# interface_board_2.net
KiCad netlist of a schematic drawn in EAGLE
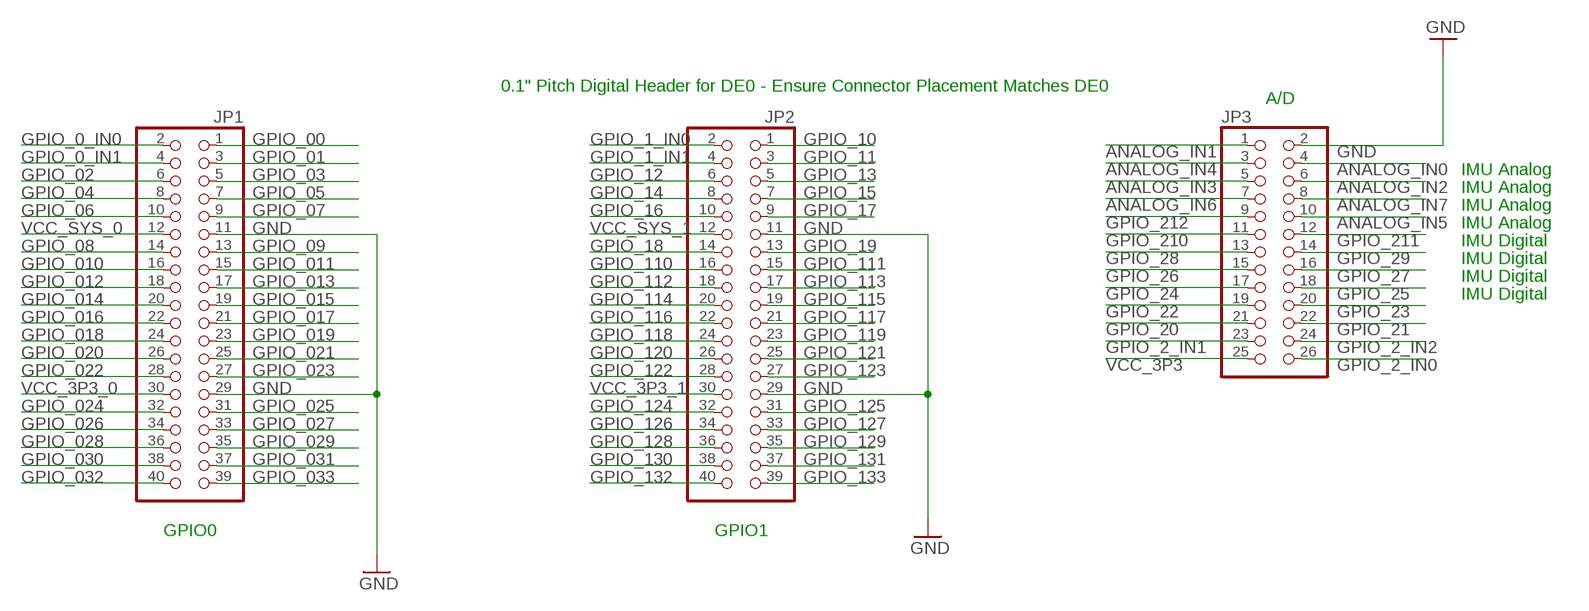
[diagram p0: schematic, sheet 1]
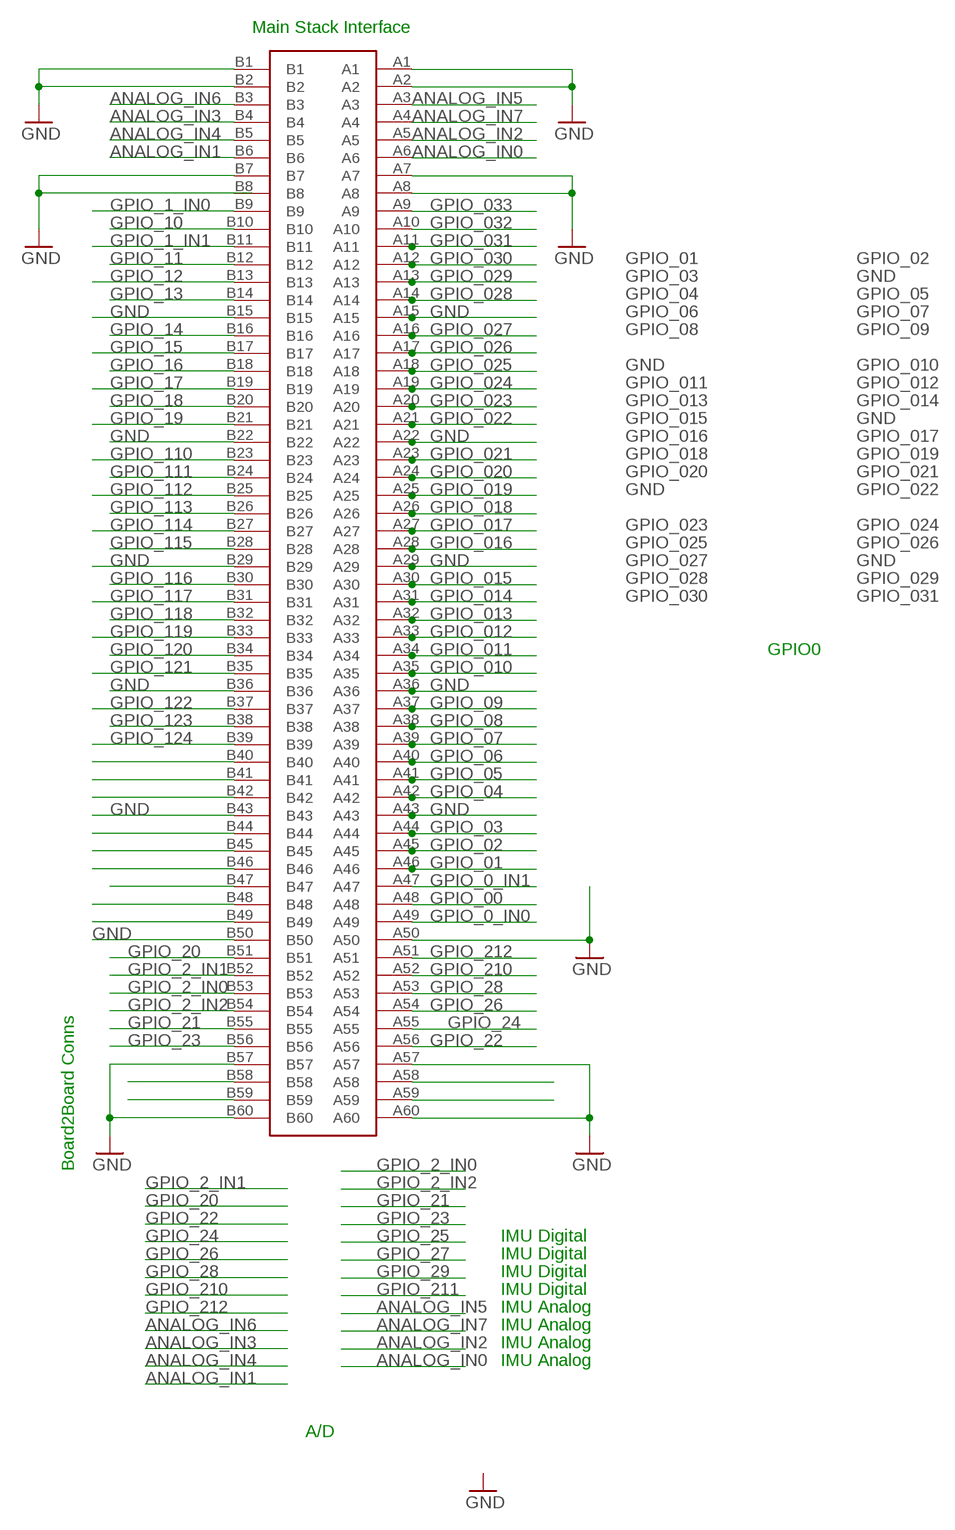
[diagram p1: schematic, sheet 2]
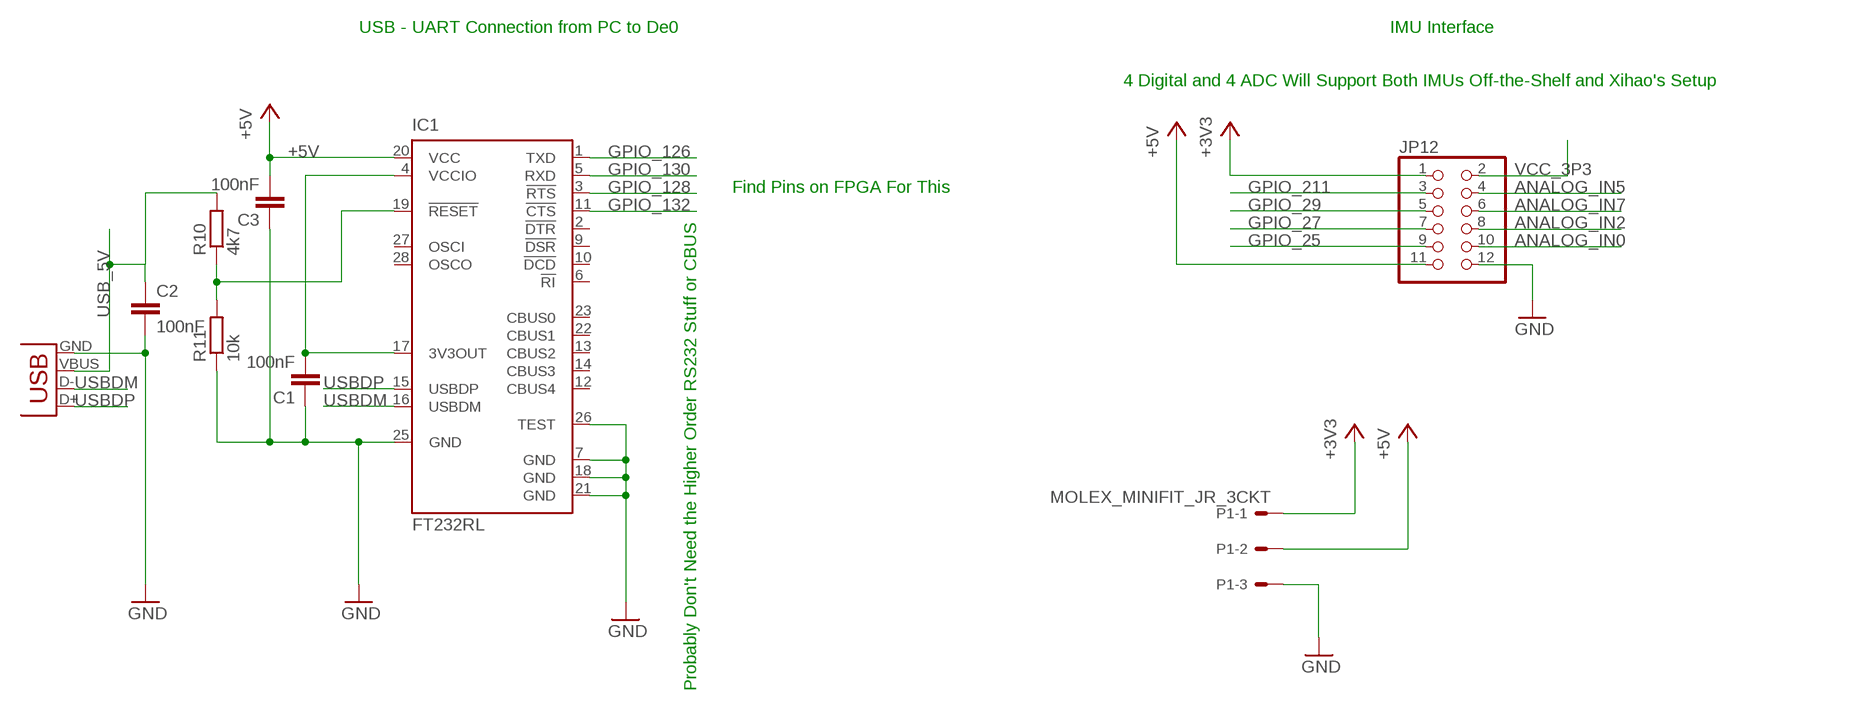
[diagram p2: schematic, sheet 3]
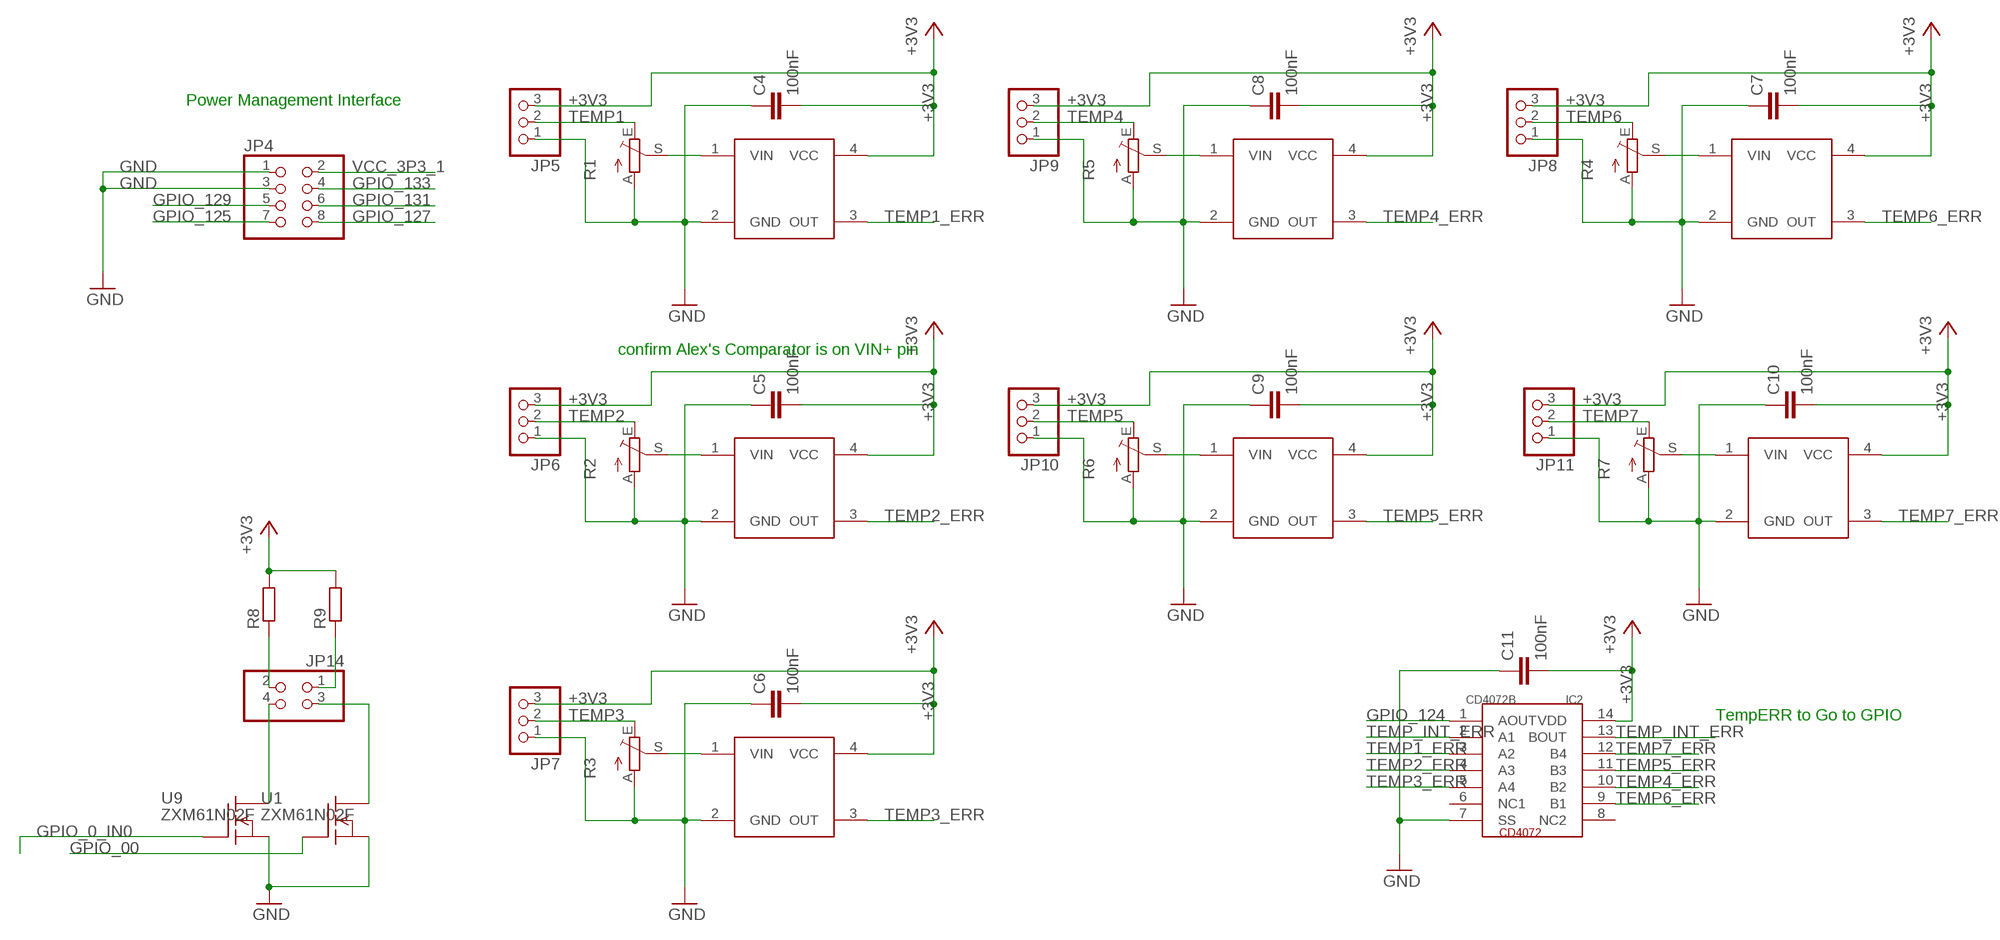
[diagram p3: schematic, sheet 4]

(export (version "E")
  (design (tool "Eeschema 10.0.6"))
  (components
    (comp (ref "C4")
      (value "100nF")
      (footprint "eagle-import:C0805")
      (libsource (lib "eagle-import") (part "C-EUC0805"))
    )
    (comp (ref "C5")
      (value "100nF")
      (footprint "eagle-import:C0805")
      (libsource (lib "eagle-import") (part "C-EUC0805"))
    )
    (comp (ref "C6")
      (value "100nF")
      (footprint "eagle-import:C0805")
      (libsource (lib "eagle-import") (part "C-EUC0805"))
    )
    (comp (ref "C7")
      (value "100nF")
      (footprint "eagle-import:C0805")
      (libsource (lib "eagle-import") (part "C-EUC0805"))
    )
    (comp (ref "C8")
      (value "100nF")
      (footprint "eagle-import:C0805")
      (libsource (lib "eagle-import") (part "C-EUC0805"))
    )
    (comp (ref "C9")
      (value "100nF")
      (footprint "eagle-import:C0805")
      (libsource (lib "eagle-import") (part "C-EUC0805"))
    )
    (comp (ref "C10")
      (value "100nF")
      (footprint "eagle-import:C0805")
      (libsource (lib "eagle-import") (part "C-EUC0805"))
    )
    (comp (ref "C11")
      (value "100nF")
      (footprint "eagle-import:C0805")
      (libsource (lib "eagle-import") (part "C-EUC0805"))
    )
    (comp (ref "IC2")
      (value "CD4072B")
      (footprint "eagle-import:SO14")
      (libsource (lib "eagle-import") (part "CD4072B"))
    )
    (comp (ref "JP4")
      (value "PINHD-2X4")
      (footprint "eagle-import:2X04")
      (libsource (lib "eagle-import") (part "PINHD-2X4"))
    )
    (comp (ref "JP5")
      (value "PINHD-1X3")
      (footprint "eagle-import:1X03")
      (libsource (lib "eagle-import") (part "PINHD-1X3"))
    )
    (comp (ref "JP6")
      (value "PINHD-1X3")
      (footprint "eagle-import:1X03")
      (libsource (lib "eagle-import") (part "PINHD-1X3"))
    )
    (comp (ref "JP7")
      (value "PINHD-1X3")
      (footprint "eagle-import:1X03")
      (libsource (lib "eagle-import") (part "PINHD-1X3"))
    )
    (comp (ref "JP8")
      (value "PINHD-1X3")
      (footprint "eagle-import:1X03")
      (libsource (lib "eagle-import") (part "PINHD-1X3"))
    )
    (comp (ref "JP9")
      (value "PINHD-1X3")
      (footprint "eagle-import:1X03")
      (libsource (lib "eagle-import") (part "PINHD-1X3"))
    )
    (comp (ref "JP10")
      (value "PINHD-1X3")
      (footprint "eagle-import:1X03")
      (libsource (lib "eagle-import") (part "PINHD-1X3"))
    )
    (comp (ref "JP11")
      (value "PINHD-1X3")
      (footprint "eagle-import:1X03")
      (libsource (lib "eagle-import") (part "PINHD-1X3"))
    )
    (comp (ref "JP14")
      (value "PINHD-2X2")
      (footprint "eagle-import:2X02")
      (libsource (lib "eagle-import") (part "PINHD-2X2"))
    )
    (comp (ref "R1")
      (value "TRIM_1234-S64YW")
      (footprint "eagle-import:POT")
      (libsource (lib "eagle-import") (part "TRIM_1234-S64YW"))
    )
    (comp (ref "R2")
      (value "TRIM_1234-S64YW")
      (footprint "eagle-import:POT")
      (libsource (lib "eagle-import") (part "TRIM_1234-S64YW"))
    )
    (comp (ref "R3")
      (value "TRIM_1234-S64YW")
      (footprint "eagle-import:POT")
      (libsource (lib "eagle-import") (part "TRIM_1234-S64YW"))
    )
    (comp (ref "R4")
      (value "TRIM_1234-S64YW")
      (footprint "eagle-import:POT")
      (libsource (lib "eagle-import") (part "TRIM_1234-S64YW"))
    )
    (comp (ref "R5")
      (value "TRIM_1234-S64YW")
      (footprint "eagle-import:POT")
      (libsource (lib "eagle-import") (part "TRIM_1234-S64YW"))
    )
    (comp (ref "R6")
      (value "TRIM_1234-S64YW")
      (footprint "eagle-import:POT")
      (libsource (lib "eagle-import") (part "TRIM_1234-S64YW"))
    )
    (comp (ref "R7")
      (value "TRIM_1234-S64YW")
      (footprint "eagle-import:POT")
      (libsource (lib "eagle-import") (part "TRIM_1234-S64YW"))
    )
    (comp (ref "R8")
      (value "R-EU_M1206")
      (footprint "eagle-import:M1206")
      (libsource (lib "eagle-import") (part "R-EU_M1206"))
    )
    (comp (ref "R9")
      (value "R-EU_M1206")
      (footprint "eagle-import:M1206")
      (libsource (lib "eagle-import") (part "R-EU_M1206"))
    )
    (comp (ref "U$2")
      (value "ADCMP")
      (footprint "eagle-import:ADCMP")
      (libsource (lib "eagle-import") (part "ADCMP"))
    )
    (comp (ref "U$4")
      (value "ADCMP")
      (footprint "eagle-import:ADCMP")
      (libsource (lib "eagle-import") (part "ADCMP"))
    )
    (comp (ref "U$5")
      (value "ADCMP")
      (footprint "eagle-import:ADCMP")
      (libsource (lib "eagle-import") (part "ADCMP"))
    )
    (comp (ref "U$6")
      (value "ADCMP")
      (footprint "eagle-import:ADCMP")
      (libsource (lib "eagle-import") (part "ADCMP"))
    )
    (comp (ref "U$7")
      (value "ADCMP")
      (footprint "eagle-import:ADCMP")
      (libsource (lib "eagle-import") (part "ADCMP"))
    )
    (comp (ref "U$8")
      (value "ADCMP")
      (footprint "eagle-import:ADCMP")
      (libsource (lib "eagle-import") (part "ADCMP"))
    )
    (comp (ref "U$9")
      (value "ADCMP")
      (footprint "eagle-import:ADCMP")
      (libsource (lib "eagle-import") (part "ADCMP"))
    )
    (comp (ref "U1")
      (value "ZXM61N02F")
      (footprint "eagle-import:SOT23W")
      (libsource (lib "eagle-import") (part "ZXM61N02F"))
    )
    (comp (ref "U9")
      (value "ZXM61N02F")
      (footprint "eagle-import:SOT23W")
      (libsource (lib "eagle-import") (part "ZXM61N02F"))
    )
    (comp (ref "JP1")
      (value "PINHD-2X20")
      (footprint "eagle-import:2X20")
      (libsource (lib "eagle-import") (part "PINHD-2X20"))
    )
    (comp (ref "JP2")
      (value "PINHD-2X20")
      (footprint "eagle-import:2X20")
      (libsource (lib "eagle-import") (part "PINHD-2X20"))
    )
    (comp (ref "JP3")
      (value "PINHD-2X13")
      (footprint "eagle-import:2X13")
      (libsource (lib "eagle-import") (part "PINHD-2X13"))
    )
    (comp (ref "U$10")
      (value "MAIN-STACK-CONN-WIDEPITCH")
      (footprint "eagle-import:STACK-CONN-WIDEPITCH")
      (libsource (lib "eagle-import") (part "MAIN-STACK-CONN-WIDEPITCH"))
    )
    (comp (ref "C1")
      (value "100nF")
      (footprint "eagle-import:C0805")
      (libsource (lib "eagle-import") (part "C-EUC0805"))
    )
    (comp (ref "C2")
      (value "100nF")
      (footprint "eagle-import:C0805")
      (libsource (lib "eagle-import") (part "C-EUC0805"))
    )
    (comp (ref "C3")
      (value "100nF")
      (footprint "eagle-import:C0805")
      (libsource (lib "eagle-import") (part "C-EUC0805"))
    )
    (comp (ref "IC1")
      (value "FT232RL")
      (footprint "eagle-import:SSOP28")
      (libsource (lib "eagle-import") (part "FT232RL"))
    )
    (comp (ref "JP12")
      (value "PINHD-2X6")
      (footprint "eagle-import:2X06")
      (libsource (lib "eagle-import") (part "PINHD-2X6"))
    )
    (comp (ref "P1")
      (value "MOLEX_MINIFIT_JR_3CKT")
      (footprint "eagle-import:3CKT_MINIFIT_JR")
      (libsource (lib "eagle-import") (part "MOLEX_MINIFIT_JR_3CKT"))
    )
    (comp (ref "R10")
      (value "4k7")
      (footprint "eagle-import:M0805")
      (libsource (lib "eagle-import") (part "R-EU_M0805"))
    )
    (comp (ref "R11")
      (value "10k")
      (footprint "eagle-import:M0805")
      (libsource (lib "eagle-import") (part "R-EU_M0805"))
    )
    (comp (ref "X1")
      (value "USBSMD")
      (footprint "eagle-import:USB-MINIB")
      (libsource (lib "eagle-import") (part "USBSMD"))
    )
  )
  (nets
    (net (code "1") (name "+3V3") (class "Default")
      (node (ref "C10") (pin "2") (pinfunction "2_2") (pintype "passive"))
      (node (ref "C11") (pin "2") (pinfunction "2_2") (pintype "passive"))
      (node (ref "C4") (pin "2") (pinfunction "2_2") (pintype "passive"))
      (node (ref "C5") (pin "2") (pinfunction "2_2") (pintype "passive"))
      (node (ref "C6") (pin "2") (pinfunction "2_2") (pintype "passive"))
      (node (ref "C7") (pin "2") (pinfunction "2_2") (pintype "passive"))
      (node (ref "C8") (pin "2") (pinfunction "2_2") (pintype "passive"))
      (node (ref "C9") (pin "2") (pinfunction "2_2") (pintype "passive"))
      (node (ref "IC2") (pin "14") (pinfunction "VDD_14") (pintype "bidirectional"))
      (node (ref "JP10") (pin "3") (pinfunction "3_3") (pintype "passive"))
      (node (ref "JP11") (pin "3") (pinfunction "3_3") (pintype "passive"))
      (node (ref "JP12") (pin "1") (pinfunction "1_1") (pintype "passive"))
      (node (ref "JP5") (pin "3") (pinfunction "3_3") (pintype "passive"))
      (node (ref "JP6") (pin "3") (pinfunction "3_3") (pintype "passive"))
      (node (ref "JP7") (pin "3") (pinfunction "3_3") (pintype "passive"))
      (node (ref "JP8") (pin "3") (pinfunction "3_3") (pintype "passive"))
      (node (ref "JP9") (pin "3") (pinfunction "3_3") (pintype "passive"))
      (node (ref "P1") (pin "1") (pinfunction "S_1") (pintype "passive"))
      (node (ref "R8") (pin "2") (pinfunction "2_2") (pintype "passive"))
      (node (ref "R9") (pin "2") (pinfunction "2_2") (pintype "passive"))
      (node (ref "U$2") (pin "4") (pinfunction "VCC_4") (pintype "bidirectional"))
      (node (ref "U$4") (pin "4") (pinfunction "VCC_4") (pintype "bidirectional"))
      (node (ref "U$5") (pin "4") (pinfunction "VCC_4") (pintype "bidirectional"))
      (node (ref "U$6") (pin "4") (pinfunction "VCC_4") (pintype "bidirectional"))
      (node (ref "U$7") (pin "4") (pinfunction "VCC_4") (pintype "bidirectional"))
      (node (ref "U$8") (pin "4") (pinfunction "VCC_4") (pintype "bidirectional"))
      (node (ref "U$9") (pin "4") (pinfunction "VCC_4") (pintype "bidirectional"))
    )
    (net (code "2") (name "+5V") (class "Default")
      (node (ref "C3") (pin "2") (pinfunction "2_2") (pintype "passive"))
      (node (ref "IC1") (pin "20") (pinfunction "VCC_20") (pintype "power_in"))
      (node (ref "JP12") (pin "11") (pinfunction "11_11") (pintype "passive"))
      (node (ref "P1") (pin "2") (pinfunction "S_2") (pintype "passive"))
    )
    (net (code "3") (name "ANALOG_IN0") (class "Default")
      (node (ref "JP12") (pin "10") (pinfunction "10_10") (pintype "passive"))
      (node (ref "JP3") (pin "4") (pinfunction "4_4") (pintype "passive"))
      (node (ref "U$10") (pin "A6") (pinfunction "A6_A6") (pintype "bidirectional"))
    )
    (net (code "4") (name "ANALOG_IN1") (class "Default")
      (node (ref "JP3") (pin "1") (pinfunction "1_1") (pintype "passive"))
      (node (ref "U$10") (pin "B6") (pinfunction "B6_B6") (pintype "bidirectional"))
    )
    (net (code "5") (name "ANALOG_IN2") (class "Default")
      (node (ref "JP12") (pin "8") (pinfunction "8_8") (pintype "passive"))
      (node (ref "JP3") (pin "6") (pinfunction "6_6") (pintype "passive"))
      (node (ref "U$10") (pin "A5") (pinfunction "A5_A5") (pintype "bidirectional"))
    )
    (net (code "6") (name "ANALOG_IN3") (class "Default")
      (node (ref "JP3") (pin "5") (pinfunction "5_5") (pintype "passive"))
      (node (ref "U$10") (pin "B4") (pinfunction "B4_B4") (pintype "bidirectional"))
    )
    (net (code "7") (name "ANALOG_IN4") (class "Default")
      (node (ref "JP3") (pin "3") (pinfunction "3_3") (pintype "passive"))
      (node (ref "U$10") (pin "B5") (pinfunction "B5_B5") (pintype "bidirectional"))
    )
    (net (code "8") (name "ANALOG_IN5") (class "Default")
      (node (ref "JP12") (pin "4") (pinfunction "4_4") (pintype "passive"))
      (node (ref "JP3") (pin "10") (pinfunction "10_10") (pintype "passive"))
      (node (ref "U$10") (pin "A3") (pinfunction "A3_A3") (pintype "bidirectional"))
    )
    (net (code "9") (name "ANALOG_IN6") (class "Default")
      (node (ref "JP3") (pin "7") (pinfunction "7_7") (pintype "passive"))
      (node (ref "U$10") (pin "B3") (pinfunction "B3_B3") (pintype "bidirectional"))
    )
    (net (code "10") (name "ANALOG_IN7") (class "Default")
      (node (ref "JP12") (pin "6") (pinfunction "6_6") (pintype "passive"))
      (node (ref "JP3") (pin "8") (pinfunction "8_8") (pintype "passive"))
      (node (ref "U$10") (pin "A4") (pinfunction "A4_A4") (pintype "bidirectional"))
    )
    (net (code "11") (name "GND") (class "Default")
      (node (ref "C1") (pin "1") (pinfunction "1_1") (pintype "passive"))
      (node (ref "C10") (pin "1") (pinfunction "1_1") (pintype "passive"))
      (node (ref "C11") (pin "1") (pinfunction "1_1") (pintype "passive"))
      (node (ref "C2") (pin "2") (pinfunction "2_2") (pintype "passive"))
      (node (ref "C3") (pin "1") (pinfunction "1_1") (pintype "passive"))
      (node (ref "C4") (pin "1") (pinfunction "1_1") (pintype "passive"))
      (node (ref "C5") (pin "1") (pinfunction "1_1") (pintype "passive"))
      (node (ref "C6") (pin "1") (pinfunction "1_1") (pintype "passive"))
      (node (ref "C7") (pin "1") (pinfunction "1_1") (pintype "passive"))
      (node (ref "C8") (pin "1") (pinfunction "1_1") (pintype "passive"))
      (node (ref "C9") (pin "1") (pinfunction "1_1") (pintype "passive"))
      (node (ref "IC1") (pin "18") (pinfunction "GND_18") (pintype "power_in"))
      (node (ref "IC1") (pin "21") (pinfunction "GND_21") (pintype "power_in"))
      (node (ref "IC1") (pin "25") (pinfunction "GND_25") (pintype "power_in"))
      (node (ref "IC1") (pin "26") (pinfunction "TEST_26") (pintype "input"))
      (node (ref "IC1") (pin "7") (pinfunction "GND_7") (pintype "power_in"))
      (node (ref "IC2") (pin "7") (pinfunction "SS_7") (pintype "bidirectional"))
      (node (ref "JP1") (pin "11") (pinfunction "11_11") (pintype "passive"))
      (node (ref "JP1") (pin "29") (pinfunction "29_29") (pintype "passive"))
      (node (ref "JP10") (pin "1") (pinfunction "1_1") (pintype "passive"))
      (node (ref "JP11") (pin "1") (pinfunction "1_1") (pintype "passive"))
      (node (ref "JP12") (pin "12") (pinfunction "12_12") (pintype "passive"))
      (node (ref "JP2") (pin "11") (pinfunction "11_11") (pintype "passive"))
      (node (ref "JP2") (pin "29") (pinfunction "29_29") (pintype "passive"))
      (node (ref "JP3") (pin "2") (pinfunction "2_2") (pintype "passive"))
      (node (ref "JP4") (pin "1") (pinfunction "1_1") (pintype "passive"))
      (node (ref "JP4") (pin "3") (pinfunction "3_3") (pintype "passive"))
      (node (ref "JP5") (pin "1") (pinfunction "1_1") (pintype "passive"))
      (node (ref "JP6") (pin "1") (pinfunction "1_1") (pintype "passive"))
      (node (ref "JP7") (pin "1") (pinfunction "1_1") (pintype "passive"))
      (node (ref "JP8") (pin "1") (pinfunction "1_1") (pintype "passive"))
      (node (ref "JP9") (pin "1") (pinfunction "1_1") (pintype "passive"))
      (node (ref "P1") (pin "3") (pinfunction "S_3") (pintype "passive"))
      (node (ref "R1") (pin "A") (pinfunction "A_A") (pintype "passive"))
      (node (ref "R11") (pin "1") (pinfunction "1_1") (pintype "passive"))
      (node (ref "R2") (pin "A") (pinfunction "A_A") (pintype "passive"))
      (node (ref "R3") (pin "A") (pinfunction "A_A") (pintype "passive"))
      (node (ref "R4") (pin "A") (pinfunction "A_A") (pintype "passive"))
      (node (ref "R5") (pin "A") (pinfunction "A_A") (pintype "passive"))
      (node (ref "R6") (pin "A") (pinfunction "A_A") (pintype "passive"))
      (node (ref "R7") (pin "A") (pinfunction "A_A") (pintype "passive"))
      (node (ref "U$10") (pin "A1") (pinfunction "A1_A1") (pintype "bidirectional"))
      (node (ref "U$10") (pin "A15") (pinfunction "A15_A15") (pintype "bidirectional"))
      (node (ref "U$10") (pin "A2") (pinfunction "A2_A2") (pintype "bidirectional"))
      (node (ref "U$10") (pin "A22") (pinfunction "A22_A22") (pintype "bidirectional"))
      (node (ref "U$10") (pin "A29") (pinfunction "A29_A29") (pintype "bidirectional"))
      (node (ref "U$10") (pin "A36") (pinfunction "A36_A36") (pintype "bidirectional"))
      (node (ref "U$10") (pin "A43") (pinfunction "A43_A43") (pintype "bidirectional"))
      (node (ref "U$10") (pin "A50") (pinfunction "A50_A50") (pintype "bidirectional"))
      (node (ref "U$10") (pin "A57") (pinfunction "A57_A57") (pintype "bidirectional"))
      (node (ref "U$10") (pin "A60") (pinfunction "A60_A60") (pintype "bidirectional"))
      (node (ref "U$10") (pin "A7") (pinfunction "A7_A7") (pintype "bidirectional"))
      (node (ref "U$10") (pin "A8") (pinfunction "A8_A8") (pintype "bidirectional"))
      (node (ref "U$10") (pin "B1") (pinfunction "B1_B1") (pintype "bidirectional"))
      (node (ref "U$10") (pin "B15") (pinfunction "B15_B15") (pintype "bidirectional"))
      (node (ref "U$10") (pin "B2") (pinfunction "B2_B2") (pintype "bidirectional"))
      (node (ref "U$10") (pin "B22") (pinfunction "B22_B22") (pintype "bidirectional"))
      (node (ref "U$10") (pin "B29") (pinfunction "B29_B29") (pintype "bidirectional"))
      (node (ref "U$10") (pin "B36") (pinfunction "B36_B36") (pintype "bidirectional"))
      (node (ref "U$10") (pin "B43") (pinfunction "B43_B43") (pintype "bidirectional"))
      (node (ref "U$10") (pin "B50") (pinfunction "B50_B50") (pintype "bidirectional"))
      (node (ref "U$10") (pin "B57") (pinfunction "B57_B57") (pintype "bidirectional"))
      (node (ref "U$10") (pin "B60") (pinfunction "B60_B60") (pintype "bidirectional"))
      (node (ref "U$10") (pin "B7") (pinfunction "B7_B7") (pintype "bidirectional"))
      (node (ref "U$2") (pin "2") (pinfunction "GND_2") (pintype "bidirectional"))
      (node (ref "U$4") (pin "2") (pinfunction "GND_2") (pintype "bidirectional"))
      (node (ref "U$5") (pin "2") (pinfunction "GND_2") (pintype "bidirectional"))
      (node (ref "U$6") (pin "2") (pinfunction "GND_2") (pintype "bidirectional"))
      (node (ref "U$7") (pin "2") (pinfunction "GND_2") (pintype "bidirectional"))
      (node (ref "U$8") (pin "2") (pinfunction "GND_2") (pintype "bidirectional"))
      (node (ref "U$9") (pin "2") (pinfunction "GND_2") (pintype "bidirectional"))
      (node (ref "U1") (pin "2") (pinfunction "S_2") (pintype "passive"))
      (node (ref "U9") (pin "2") (pinfunction "S_2") (pintype "passive"))
      (node (ref "X1") (pin "GND") (pinfunction "GND_GND") (pintype "bidirectional"))
    )
    (net (code "12") (name "GPIO_00") (class "Default")
      (node (ref "JP1") (pin "1") (pinfunction "1_1") (pintype "passive"))
      (node (ref "U$10") (pin "A48") (pinfunction "A48_A48") (pintype "bidirectional"))
      (node (ref "U1") (pin "1") (pinfunction "G_1") (pintype "passive"))
    )
    (net (code "13") (name "GPIO_0_IN0") (class "Default")
      (node (ref "JP1") (pin "2") (pinfunction "2_2") (pintype "passive"))
      (node (ref "U$10") (pin "A49") (pinfunction "A49_A49") (pintype "bidirectional"))
      (node (ref "U9") (pin "1") (pinfunction "G_1") (pintype "passive"))
    )
    (net (code "14") (name "GPIO_0_IN1") (class "Default")
      (node (ref "JP1") (pin "4") (pinfunction "4_4") (pintype "passive"))
      (node (ref "U$10") (pin "A47") (pinfunction "A47_A47") (pintype "bidirectional"))
    )
    (net (code "15") (name "GPIO_01") (class "Default")
      (node (ref "JP1") (pin "3") (pinfunction "3_3") (pintype "passive"))
      (node (ref "U$10") (pin "A46") (pinfunction "A46_A46") (pintype "bidirectional"))
    )
    (net (code "16") (name "GPIO_1_IN0") (class "Default")
      (node (ref "JP2") (pin "2") (pinfunction "2_2") (pintype "passive"))
      (node (ref "U$10") (pin "B9") (pinfunction "B9_B9") (pintype "bidirectional"))
    )
    (net (code "17") (name "GPIO_1_IN1") (class "Default")
      (node (ref "JP2") (pin "4") (pinfunction "4_4") (pintype "passive"))
      (node (ref "U$10") (pin "B11") (pinfunction "B11_B11") (pintype "bidirectional"))
    )
    (net (code "18") (name "GPIO_02") (class "Default")
      (node (ref "JP1") (pin "6") (pinfunction "6_6") (pintype "passive"))
      (node (ref "U$10") (pin "A45") (pinfunction "A45_A45") (pintype "bidirectional"))
    )
    (net (code "19") (name "GPIO_2_IN0") (class "Default")
      (node (ref "JP3") (pin "26") (pinfunction "26_26") (pintype "passive"))
      (node (ref "U$10") (pin "B53") (pinfunction "B53_B53") (pintype "bidirectional"))
    )
    (net (code "20") (name "GPIO_2_IN1") (class "Default")
      (node (ref "JP3") (pin "23") (pinfunction "23_23") (pintype "passive"))
      (node (ref "U$10") (pin "B52") (pinfunction "B52_B52") (pintype "bidirectional"))
    )
    (net (code "21") (name "GPIO_2_IN2") (class "Default")
      (node (ref "JP3") (pin "24") (pinfunction "24_24") (pintype "passive"))
      (node (ref "U$10") (pin "B54") (pinfunction "B54_B54") (pintype "bidirectional"))
    )
    (net (code "22") (name "GPIO_03") (class "Default")
      (node (ref "JP1") (pin "5") (pinfunction "5_5") (pintype "passive"))
      (node (ref "U$10") (pin "A44") (pinfunction "A44_A44") (pintype "bidirectional"))
    )
    (net (code "23") (name "GPIO_04") (class "Default")
      (node (ref "JP1") (pin "8") (pinfunction "8_8") (pintype "passive"))
      (node (ref "U$10") (pin "A42") (pinfunction "A42_A42") (pintype "bidirectional"))
    )
    (net (code "24") (name "GPIO_05") (class "Default")
      (node (ref "JP1") (pin "7") (pinfunction "7_7") (pintype "passive"))
      (node (ref "U$10") (pin "A41") (pinfunction "A41_A41") (pintype "bidirectional"))
    )
    (net (code "25") (name "GPIO_06") (class "Default")
      (node (ref "JP1") (pin "10") (pinfunction "10_10") (pintype "passive"))
      (node (ref "U$10") (pin "A40") (pinfunction "A40_A40") (pintype "bidirectional"))
    )
    (net (code "26") (name "GPIO_07") (class "Default")
      (node (ref "JP1") (pin "9") (pinfunction "9_9") (pintype "passive"))
      (node (ref "U$10") (pin "A39") (pinfunction "A39_A39") (pintype "bidirectional"))
    )
    (net (code "27") (name "GPIO_08") (class "Default")
      (node (ref "JP1") (pin "14") (pinfunction "14_14") (pintype "passive"))
      (node (ref "U$10") (pin "A38") (pinfunction "A38_A38") (pintype "bidirectional"))
    )
    (net (code "28") (name "GPIO_09") (class "Default")
      (node (ref "JP1") (pin "13") (pinfunction "13_13") (pintype "passive"))
      (node (ref "U$10") (pin "A37") (pinfunction "A37_A37") (pintype "bidirectional"))
    )
    (net (code "29") (name "GPIO_10") (class "Default")
      (node (ref "JP2") (pin "1") (pinfunction "1_1") (pintype "passive"))
      (node (ref "U$10") (pin "B10") (pinfunction "B10_B10") (pintype "bidirectional"))
    )
    (net (code "30") (name "GPIO_010") (class "Default")
      (node (ref "JP1") (pin "16") (pinfunction "16_16") (pintype "passive"))
      (node (ref "U$10") (pin "A35") (pinfunction "A35_A35") (pintype "bidirectional"))
    )
    (net (code "31") (name "GPIO_11") (class "Default")
      (node (ref "JP2") (pin "3") (pinfunction "3_3") (pintype "passive"))
      (node (ref "U$10") (pin "B12") (pinfunction "B12_B12") (pintype "bidirectional"))
    )
    (net (code "32") (name "GPIO_011") (class "Default")
      (node (ref "JP1") (pin "15") (pinfunction "15_15") (pintype "passive"))
      (node (ref "U$10") (pin "A34") (pinfunction "A34_A34") (pintype "bidirectional"))
    )
    (net (code "33") (name "GPIO_12") (class "Default")
      (node (ref "JP2") (pin "6") (pinfunction "6_6") (pintype "passive"))
      (node (ref "U$10") (pin "B13") (pinfunction "B13_B13") (pintype "bidirectional"))
    )
    (net (code "34") (name "GPIO_012") (class "Default")
      (node (ref "JP1") (pin "18") (pinfunction "18_18") (pintype "passive"))
      (node (ref "U$10") (pin "A33") (pinfunction "A33_A33") (pintype "bidirectional"))
    )
    (net (code "35") (name "GPIO_013") (class "Default")
      (node (ref "JP1") (pin "17") (pinfunction "17_17") (pintype "passive"))
      (node (ref "U$10") (pin "A32") (pinfunction "A32_A32") (pintype "bidirectional"))
    )
    (net (code "36") (name "GPIO_13") (class "Default")
      (node (ref "JP2") (pin "5") (pinfunction "5_5") (pintype "passive"))
      (node (ref "U$10") (pin "B14") (pinfunction "B14_B14") (pintype "bidirectional"))
    )
    (net (code "37") (name "GPIO_14") (class "Default")
      (node (ref "JP2") (pin "8") (pinfunction "8_8") (pintype "passive"))
      (node (ref "U$10") (pin "B16") (pinfunction "B16_B16") (pintype "bidirectional"))
    )
    (net (code "38") (name "GPIO_014") (class "Default")
      (node (ref "JP1") (pin "20") (pinfunction "20_20") (pintype "passive"))
      (node (ref "U$10") (pin "A31") (pinfunction "A31_A31") (pintype "bidirectional"))
    )
    (net (code "39") (name "GPIO_015") (class "Default")
      (node (ref "JP1") (pin "19") (pinfunction "19_19") (pintype "passive"))
      (node (ref "U$10") (pin "A30") (pinfunction "A30_A30") (pintype "bidirectional"))
    )
    (net (code "40") (name "GPIO_15") (class "Default")
      (node (ref "JP2") (pin "7") (pinfunction "7_7") (pintype "passive"))
      (node (ref "U$10") (pin "B17") (pinfunction "B17_B17") (pintype "bidirectional"))
    )
    (net (code "41") (name "GPIO_016") (class "Default")
      (node (ref "JP1") (pin "22") (pinfunction "22_22") (pintype "passive"))
      (node (ref "U$10") (pin "A28") (pinfunction "A28_A28") (pintype "bidirectional"))
    )
    (net (code "42") (name "GPIO_16") (class "Default")
      (node (ref "JP2") (pin "10") (pinfunction "10_10") (pintype "passive"))
      (node (ref "U$10") (pin "B18") (pinfunction "B18_B18") (pintype "bidirectional"))
    )
    (net (code "43") (name "GPIO_017") (class "Default")
      (node (ref "JP1") (pin "21") (pinfunction "21_21") (pintype "passive"))
      (node (ref "U$10") (pin "A27") (pinfunction "A27_A27") (pintype "bidirectional"))
    )
    (net (code "44") (name "GPIO_17") (class "Default")
      (node (ref "JP2") (pin "9") (pinfunction "9_9") (pintype "passive"))
      (node (ref "U$10") (pin "B19") (pinfunction "B19_B19") (pintype "bidirectional"))
    )
    (net (code "45") (name "GPIO_018") (class "Default")
      (node (ref "JP1") (pin "24") (pinfunction "24_24") (pintype "passive"))
      (node (ref "U$10") (pin "A26") (pinfunction "A26_A26") (pintype "bidirectional"))
    )
    (net (code "46") (name "GPIO_18") (class "Default")
      (node (ref "JP2") (pin "14") (pinfunction "14_14") (pintype "passive"))
      (node (ref "U$10") (pin "B20") (pinfunction "B20_B20") (pintype "bidirectional"))
    )
    (net (code "47") (name "GPIO_19") (class "Default")
      (node (ref "JP2") (pin "13") (pinfunction "13_13") (pintype "passive"))
      (node (ref "U$10") (pin "B21") (pinfunction "B21_B21") (pintype "bidirectional"))
    )
    (net (code "48") (name "GPIO_019") (class "Default")
      (node (ref "JP1") (pin "23") (pinfunction "23_23") (pintype "passive"))
      (node (ref "U$10") (pin "A25") (pinfunction "A25_A25") (pintype "bidirectional"))
    )
    (net (code "49") (name "GPIO_20") (class "Default")
      (node (ref "JP3") (pin "21") (pinfunction "21_21") (pintype "passive"))
      (node (ref "U$10") (pin "B51") (pinfunction "B51_B51") (pintype "bidirectional"))
    )
    (net (code "50") (name "GPIO_020") (class "Default")
      (node (ref "JP1") (pin "26") (pinfunction "26_26") (pintype "passive"))
      (node (ref "U$10") (pin "A24") (pinfunction "A24_A24") (pintype "bidirectional"))
    )
    (net (code "51") (name "GPIO_021") (class "Default")
      (node (ref "JP1") (pin "25") (pinfunction "25_25") (pintype "passive"))
      (node (ref "U$10") (pin "A23") (pinfunction "A23_A23") (pintype "bidirectional"))
    )
    (net (code "52") (name "GPIO_21") (class "Default")
      (node (ref "JP3") (pin "22") (pinfunction "22_22") (pintype "passive"))
      (node (ref "U$10") (pin "B55") (pinfunction "B55_B55") (pintype "bidirectional"))
    )
    (net (code "53") (name "GPIO_022") (class "Default")
      (node (ref "JP1") (pin "28") (pinfunction "28_28") (pintype "passive"))
      (node (ref "U$10") (pin "A21") (pinfunction "A21_A21") (pintype "bidirectional"))
    )
    (net (code "54") (name "GPIO_22") (class "Default")
      (node (ref "JP3") (pin "19") (pinfunction "19_19") (pintype "passive"))
      (node (ref "U$10") (pin "A56") (pinfunction "A56_A56") (pintype "bidirectional"))
    )
    (net (code "55") (name "GPIO_23") (class "Default")
      (node (ref "JP3") (pin "20") (pinfunction "20_20") (pintype "passive"))
      (node (ref "U$10") (pin "B56") (pinfunction "B56_B56") (pintype "bidirectional"))
    )
    (net (code "56") (name "GPIO_023") (class "Default")
      (node (ref "JP1") (pin "27") (pinfunction "27_27") (pintype "passive"))
      (node (ref "U$10") (pin "A20") (pinfunction "A20_A20") (pintype "bidirectional"))
    )
    (net (code "57") (name "GPIO_24") (class "Default")
      (node (ref "JP3") (pin "17") (pinfunction "17_17") (pintype "passive"))
      (node (ref "U$10") (pin "A55") (pinfunction "A55_A55") (pintype "bidirectional"))
    )
    (net (code "58") (name "GPIO_024") (class "Default")
      (node (ref "JP1") (pin "32") (pinfunction "32_32") (pintype "passive"))
      (node (ref "U$10") (pin "A19") (pinfunction "A19_A19") (pintype "bidirectional"))
    )
    (net (code "59") (name "GPIO_025") (class "Default")
      (node (ref "JP1") (pin "31") (pinfunction "31_31") (pintype "passive"))
      (node (ref "U$10") (pin "A18") (pinfunction "A18_A18") (pintype "bidirectional"))
    )
    (net (code "60") (name "GPIO_25") (class "Default")
      (node (ref "JP12") (pin "9") (pinfunction "9_9") (pintype "passive"))
      (node (ref "JP3") (pin "18") (pinfunction "18_18") (pintype "passive"))
    )
    (net (code "61") (name "GPIO_026") (class "Default")
      (node (ref "JP1") (pin "34") (pinfunction "34_34") (pintype "passive"))
      (node (ref "U$10") (pin "A17") (pinfunction "A17_A17") (pintype "bidirectional"))
    )
    (net (code "62") (name "GPIO_26") (class "Default")
      (node (ref "JP3") (pin "15") (pinfunction "15_15") (pintype "passive"))
      (node (ref "U$10") (pin "A54") (pinfunction "A54_A54") (pintype "bidirectional"))
    )
    (net (code "63") (name "GPIO_27") (class "Default")
      (node (ref "JP12") (pin "7") (pinfunction "7_7") (pintype "passive"))
      (node (ref "JP3") (pin "16") (pinfunction "16_16") (pintype "passive"))
    )
    (net (code "64") (name "GPIO_027") (class "Default")
      (node (ref "JP1") (pin "33") (pinfunction "33_33") (pintype "passive"))
      (node (ref "U$10") (pin "A16") (pinfunction "A16_A16") (pintype "bidirectional"))
    )
    (net (code "65") (name "GPIO_28") (class "Default")
      (node (ref "JP3") (pin "13") (pinfunction "13_13") (pintype "passive"))
      (node (ref "U$10") (pin "A53") (pinfunction "A53_A53") (pintype "bidirectional"))
    )
    (net (code "66") (name "GPIO_028") (class "Default")
      (node (ref "JP1") (pin "36") (pinfunction "36_36") (pintype "passive"))
      (node (ref "U$10") (pin "A14") (pinfunction "A14_A14") (pintype "bidirectional"))
    )
    (net (code "67") (name "GPIO_29") (class "Default")
      (node (ref "JP12") (pin "5") (pinfunction "5_5") (pintype "passive"))
      (node (ref "JP3") (pin "14") (pinfunction "14_14") (pintype "passive"))
    )
    (net (code "68") (name "GPIO_029") (class "Default")
      (node (ref "JP1") (pin "35") (pinfunction "35_35") (pintype "passive"))
      (node (ref "U$10") (pin "A13") (pinfunction "A13_A13") (pintype "bidirectional"))
    )
    (net (code "69") (name "GPIO_030") (class "Default")
      (node (ref "JP1") (pin "38") (pinfunction "38_38") (pintype "passive"))
      (node (ref "U$10") (pin "A12") (pinfunction "A12_A12") (pintype "bidirectional"))
    )
    (net (code "70") (name "GPIO_031") (class "Default")
      (node (ref "JP1") (pin "37") (pinfunction "37_37") (pintype "passive"))
      (node (ref "U$10") (pin "A11") (pinfunction "A11_A11") (pintype "bidirectional"))
    )
    (net (code "71") (name "GPIO_032") (class "Default")
      (node (ref "JP1") (pin "40") (pinfunction "40_40") (pintype "passive"))
      (node (ref "U$10") (pin "A10") (pinfunction "A10_A10") (pintype "bidirectional"))
    )
    (net (code "72") (name "GPIO_033") (class "Default")
      (node (ref "JP1") (pin "39") (pinfunction "39_39") (pintype "passive"))
      (node (ref "U$10") (pin "A9") (pinfunction "A9_A9") (pintype "bidirectional"))
    )
    (net (code "73") (name "GPIO_110") (class "Default")
      (node (ref "JP2") (pin "16") (pinfunction "16_16") (pintype "passive"))
      (node (ref "U$10") (pin "B23") (pinfunction "B23_B23") (pintype "bidirectional"))
    )
    (net (code "74") (name "GPIO_111") (class "Default")
      (node (ref "JP2") (pin "15") (pinfunction "15_15") (pintype "passive"))
      (node (ref "U$10") (pin "B24") (pinfunction "B24_B24") (pintype "bidirectional"))
    )
    (net (code "75") (name "GPIO_112") (class "Default")
      (node (ref "JP2") (pin "18") (pinfunction "18_18") (pintype "passive"))
      (node (ref "U$10") (pin "B25") (pinfunction "B25_B25") (pintype "bidirectional"))
    )
    (net (code "76") (name "GPIO_113") (class "Default")
      (node (ref "JP2") (pin "17") (pinfunction "17_17") (pintype "passive"))
      (node (ref "U$10") (pin "B26") (pinfunction "B26_B26") (pintype "bidirectional"))
    )
    (net (code "77") (name "GPIO_114") (class "Default")
      (node (ref "JP2") (pin "20") (pinfunction "20_20") (pintype "passive"))
      (node (ref "U$10") (pin "B27") (pinfunction "B27_B27") (pintype "bidirectional"))
    )
    (net (code "78") (name "GPIO_115") (class "Default")
      (node (ref "JP2") (pin "19") (pinfunction "19_19") (pintype "passive"))
      (node (ref "U$10") (pin "B28") (pinfunction "B28_B28") (pintype "bidirectional"))
    )
    (net (code "79") (name "GPIO_116") (class "Default")
      (node (ref "JP2") (pin "22") (pinfunction "22_22") (pintype "passive"))
      (node (ref "U$10") (pin "B30") (pinfunction "B30_B30") (pintype "bidirectional"))
    )
    (net (code "80") (name "GPIO_117") (class "Default")
      (node (ref "JP2") (pin "21") (pinfunction "21_21") (pintype "passive"))
      (node (ref "U$10") (pin "B31") (pinfunction "B31_B31") (pintype "bidirectional"))
    )
    (net (code "81") (name "GPIO_118") (class "Default")
      (node (ref "JP2") (pin "24") (pinfunction "24_24") (pintype "passive"))
      (node (ref "U$10") (pin "B32") (pinfunction "B32_B32") (pintype "bidirectional"))
    )
    (net (code "82") (name "GPIO_119") (class "Default")
      (node (ref "JP2") (pin "23") (pinfunction "23_23") (pintype "passive"))
      (node (ref "U$10") (pin "B33") (pinfunction "B33_B33") (pintype "bidirectional"))
    )
    (net (code "83") (name "GPIO_120") (class "Default")
      (node (ref "JP2") (pin "26") (pinfunction "26_26") (pintype "passive"))
      (node (ref "U$10") (pin "B34") (pinfunction "B34_B34") (pintype "bidirectional"))
    )
    (net (code "84") (name "GPIO_121") (class "Default")
      (node (ref "JP2") (pin "25") (pinfunction "25_25") (pintype "passive"))
      (node (ref "U$10") (pin "B35") (pinfunction "B35_B35") (pintype "bidirectional"))
    )
    (net (code "85") (name "GPIO_122") (class "Default")
      (node (ref "JP2") (pin "28") (pinfunction "28_28") (pintype "passive"))
      (node (ref "U$10") (pin "B37") (pinfunction "B37_B37") (pintype "bidirectional"))
    )
    (net (code "86") (name "GPIO_123") (class "Default")
      (node (ref "JP2") (pin "27") (pinfunction "27_27") (pintype "passive"))
      (node (ref "U$10") (pin "B38") (pinfunction "B38_B38") (pintype "bidirectional"))
    )
    (net (code "87") (name "GPIO_124") (class "Default")
      (node (ref "IC2") (pin "1") (pinfunction "AOUT_1") (pintype "bidirectional"))
      (node (ref "JP2") (pin "32") (pinfunction "32_32") (pintype "passive"))
      (node (ref "U$10") (pin "B39") (pinfunction "B39_B39") (pintype "bidirectional"))
    )
    (net (code "88") (name "GPIO_125") (class "Default")
      (node (ref "JP2") (pin "31") (pinfunction "31_31") (pintype "passive"))
      (node (ref "JP4") (pin "7") (pinfunction "7_7") (pintype "passive"))
    )
    (net (code "89") (name "GPIO_126") (class "Default")
      (node (ref "IC1") (pin "1") (pinfunction "TXD_1") (pintype "output"))
      (node (ref "JP2") (pin "34") (pinfunction "34_34") (pintype "passive"))
    )
    (net (code "90") (name "GPIO_127") (class "Default")
      (node (ref "JP2") (pin "33") (pinfunction "33_33") (pintype "passive"))
      (node (ref "JP4") (pin "8") (pinfunction "8_8") (pintype "passive"))
    )
    (net (code "91") (name "GPIO_128") (class "Default")
      (node (ref "IC1") (pin "3") (pinfunction "~{RTS}_3") (pintype "output"))
      (node (ref "JP2") (pin "36") (pinfunction "36_36") (pintype "passive"))
    )
    (net (code "92") (name "GPIO_129") (class "Default")
      (node (ref "JP2") (pin "35") (pinfunction "35_35") (pintype "passive"))
      (node (ref "JP4") (pin "5") (pinfunction "5_5") (pintype "passive"))
    )
    (net (code "93") (name "GPIO_130") (class "Default")
      (node (ref "IC1") (pin "5") (pinfunction "RXD_5") (pintype "input"))
      (node (ref "JP2") (pin "38") (pinfunction "38_38") (pintype "passive"))
    )
    (net (code "94") (name "GPIO_131") (class "Default")
      (node (ref "JP2") (pin "37") (pinfunction "37_37") (pintype "passive"))
      (node (ref "JP4") (pin "6") (pinfunction "6_6") (pintype "passive"))
    )
    (net (code "95") (name "GPIO_132") (class "Default")
      (node (ref "IC1") (pin "11") (pinfunction "~{CTS}_11") (pintype "input"))
      (node (ref "JP2") (pin "40") (pinfunction "40_40") (pintype "passive"))
    )
    (net (code "96") (name "GPIO_133") (class "Default")
      (node (ref "JP2") (pin "39") (pinfunction "39_39") (pintype "passive"))
      (node (ref "JP4") (pin "4") (pinfunction "4_4") (pintype "passive"))
    )
    (net (code "97") (name "GPIO_210") (class "Default")
      (node (ref "JP3") (pin "11") (pinfunction "11_11") (pintype "passive"))
      (node (ref "U$10") (pin "A52") (pinfunction "A52_A52") (pintype "bidirectional"))
    )
    (net (code "98") (name "GPIO_211") (class "Default")
      (node (ref "JP12") (pin "3") (pinfunction "3_3") (pintype "passive"))
      (node (ref "JP3") (pin "12") (pinfunction "12_12") (pintype "passive"))
    )
    (net (code "99") (name "GPIO_212") (class "Default")
      (node (ref "JP3") (pin "9") (pinfunction "9_9") (pintype "passive"))
      (node (ref "U$10") (pin "A51") (pinfunction "A51_A51") (pintype "bidirectional"))
    )
    (net (code "100") (name "Net-(IC1-3V3OUT)") (class "Default")
      (node (ref "C1") (pin "2") (pinfunction "2_2") (pintype "passive"))
      (node (ref "IC1") (pin "17") (pinfunction "3V3OUT_17") (pintype "output"))
      (node (ref "IC1") (pin "4") (pinfunction "VCCIO_4") (pintype "power_in"))
    )
    (net (code "101") (name "Net-(IC1-~{RESET})") (class "Default")
      (node (ref "IC1") (pin "19") (pinfunction "~{RESET}_19") (pintype "input"))
      (node (ref "R10") (pin "1") (pinfunction "1_1") (pintype "passive"))
      (node (ref "R11") (pin "2") (pinfunction "2_2") (pintype "passive"))
    )
    (net (code "102") (name "Net-(JP14-Pad1)") (class "Default")
      (node (ref "JP14") (pin "1") (pinfunction "1_1") (pintype "passive"))
      (node (ref "R9") (pin "1") (pinfunction "1_1") (pintype "passive"))
    )
    (net (code "103") (name "Net-(JP14-Pad2)") (class "Default")
      (node (ref "JP14") (pin "2") (pinfunction "2_2") (pintype "passive"))
      (node (ref "R8") (pin "1") (pinfunction "1_1") (pintype "passive"))
    )
    (net (code "104") (name "Net-(U$2-VIN)") (class "Default")
      (node (ref "R1") (pin "S") (pinfunction "S_S") (pintype "passive"))
      (node (ref "U$2") (pin "1") (pinfunction "VIN_1") (pintype "bidirectional"))
    )
    (net (code "105") (name "Net-(U$4-VIN)") (class "Default")
      (node (ref "R2") (pin "S") (pinfunction "S_S") (pintype "passive"))
      (node (ref "U$4") (pin "1") (pinfunction "VIN_1") (pintype "bidirectional"))
    )
    (net (code "106") (name "Net-(U$5-VIN)") (class "Default")
      (node (ref "R3") (pin "S") (pinfunction "S_S") (pintype "passive"))
      (node (ref "U$5") (pin "1") (pinfunction "VIN_1") (pintype "bidirectional"))
    )
    (net (code "107") (name "Net-(U$6-VIN)") (class "Default")
      (node (ref "R4") (pin "S") (pinfunction "S_S") (pintype "passive"))
      (node (ref "U$6") (pin "1") (pinfunction "VIN_1") (pintype "bidirectional"))
    )
    (net (code "108") (name "Net-(U$7-VIN)") (class "Default")
      (node (ref "R5") (pin "S") (pinfunction "S_S") (pintype "passive"))
      (node (ref "U$7") (pin "1") (pinfunction "VIN_1") (pintype "bidirectional"))
    )
    (net (code "109") (name "Net-(U$8-VIN)") (class "Default")
      (node (ref "R6") (pin "S") (pinfunction "S_S") (pintype "passive"))
      (node (ref "U$8") (pin "1") (pinfunction "VIN_1") (pintype "bidirectional"))
    )
    (net (code "110") (name "Net-(U$9-VIN)") (class "Default")
      (node (ref "R7") (pin "S") (pinfunction "S_S") (pintype "passive"))
      (node (ref "U$9") (pin "1") (pinfunction "VIN_1") (pintype "bidirectional"))
    )
    (net (code "111") (name "Net-(U1-D)") (class "Default")
      (node (ref "JP14") (pin "3") (pinfunction "3_3") (pintype "passive"))
      (node (ref "U1") (pin "3") (pinfunction "D_3") (pintype "passive"))
    )
    (net (code "112") (name "Net-(U9-D)") (class "Default")
      (node (ref "JP14") (pin "4") (pinfunction "4_4") (pintype "passive"))
      (node (ref "U9") (pin "3") (pinfunction "D_3") (pintype "passive"))
    )
    (net (code "113") (name "TEMP1") (class "Default")
      (node (ref "JP5") (pin "2") (pinfunction "2_2") (pintype "passive"))
      (node (ref "R1") (pin "E") (pinfunction "E_E") (pintype "passive"))
    )
    (net (code "114") (name "TEMP1_ERR") (class "Default")
      (node (ref "IC2") (pin "3") (pinfunction "A2_3") (pintype "bidirectional"))
      (node (ref "U$2") (pin "3") (pinfunction "OUT_3") (pintype "bidirectional"))
    )
    (net (code "115") (name "TEMP2") (class "Default")
      (node (ref "JP6") (pin "2") (pinfunction "2_2") (pintype "passive"))
      (node (ref "R2") (pin "E") (pinfunction "E_E") (pintype "passive"))
    )
    (net (code "116") (name "TEMP2_ERR") (class "Default")
      (node (ref "IC2") (pin "4") (pinfunction "A3_4") (pintype "bidirectional"))
      (node (ref "U$4") (pin "3") (pinfunction "OUT_3") (pintype "bidirectional"))
    )
    (net (code "117") (name "TEMP3") (class "Default")
      (node (ref "JP7") (pin "2") (pinfunction "2_2") (pintype "passive"))
      (node (ref "R3") (pin "E") (pinfunction "E_E") (pintype "passive"))
    )
    (net (code "118") (name "TEMP3_ERR") (class "Default")
      (node (ref "IC2") (pin "5") (pinfunction "A4_5") (pintype "bidirectional"))
      (node (ref "U$5") (pin "3") (pinfunction "OUT_3") (pintype "bidirectional"))
    )
    (net (code "119") (name "TEMP4") (class "Default")
      (node (ref "JP9") (pin "2") (pinfunction "2_2") (pintype "passive"))
      (node (ref "R5") (pin "E") (pinfunction "E_E") (pintype "passive"))
    )
    (net (code "120") (name "TEMP4_ERR") (class "Default")
      (node (ref "IC2") (pin "10") (pinfunction "B2_10") (pintype "bidirectional"))
      (node (ref "U$7") (pin "3") (pinfunction "OUT_3") (pintype "bidirectional"))
    )
    (net (code "121") (name "TEMP5") (class "Default")
      (node (ref "JP10") (pin "2") (pinfunction "2_2") (pintype "passive"))
      (node (ref "R6") (pin "E") (pinfunction "E_E") (pintype "passive"))
    )
    (net (code "122") (name "TEMP5_ERR") (class "Default")
      (node (ref "IC2") (pin "11") (pinfunction "B3_11") (pintype "bidirectional"))
      (node (ref "U$8") (pin "3") (pinfunction "OUT_3") (pintype "bidirectional"))
    )
    (net (code "123") (name "TEMP6") (class "Default")
      (node (ref "JP8") (pin "2") (pinfunction "2_2") (pintype "passive"))
      (node (ref "R4") (pin "E") (pinfunction "E_E") (pintype "passive"))
    )
    (net (code "124") (name "TEMP6_ERR") (class "Default")
      (node (ref "IC2") (pin "9") (pinfunction "B1_9") (pintype "bidirectional"))
      (node (ref "U$6") (pin "3") (pinfunction "OUT_3") (pintype "bidirectional"))
    )
    (net (code "125") (name "TEMP7") (class "Default")
      (node (ref "JP11") (pin "2") (pinfunction "2_2") (pintype "passive"))
      (node (ref "R7") (pin "E") (pinfunction "E_E") (pintype "passive"))
    )
    (net (code "126") (name "TEMP7_ERR") (class "Default")
      (node (ref "IC2") (pin "12") (pinfunction "B4_12") (pintype "bidirectional"))
      (node (ref "U$9") (pin "3") (pinfunction "OUT_3") (pintype "bidirectional"))
    )
    (net (code "127") (name "TEMP_INT_ERR") (class "Default")
      (node (ref "IC2") (pin "13") (pinfunction "BOUT_13") (pintype "bidirectional"))
      (node (ref "IC2") (pin "2") (pinfunction "A1_2") (pintype "bidirectional"))
    )
    (net (code "128") (name "USBDM") (class "Default")
      (node (ref "IC1") (pin "16") (pinfunction "USBDM_16") (pintype "bidirectional"))
      (node (ref "X1") (pin "D-") (pinfunction "D-_D-") (pintype "bidirectional"))
    )
    (net (code "129") (name "USBDP") (class "Default")
      (node (ref "IC1") (pin "15") (pinfunction "USBDP_15") (pintype "bidirectional"))
      (node (ref "X1") (pin "D+") (pinfunction "D+_D+") (pintype "bidirectional"))
    )
    (net (code "130") (name "USB_5V") (class "Default")
      (node (ref "C2") (pin "1") (pinfunction "1_1") (pintype "passive"))
      (node (ref "R10") (pin "2") (pinfunction "2_2") (pintype "passive"))
      (node (ref "X1") (pin "VBUS") (pinfunction "VBUS_VBUS") (pintype "bidirectional"))
    )
    (net (code "131") (name "VCC_3P3") (class "Default")
      (node (ref "JP12") (pin "2") (pinfunction "2_2") (pintype "passive"))
      (node (ref "JP3") (pin "25") (pinfunction "25_25") (pintype "passive"))
    )
    (net (code "132") (name "VCC_3P3_0") (class "Default")
      (node (ref "JP1") (pin "30") (pinfunction "30_30") (pintype "passive"))
    )
    (net (code "133") (name "VCC_3P3_1") (class "Default")
      (node (ref "JP2") (pin "30") (pinfunction "30_30") (pintype "passive"))
      (node (ref "JP4") (pin "2") (pinfunction "2_2") (pintype "passive"))
    )
    (net (code "134") (name "VCC_SYS_0") (class "Default")
      (node (ref "JP1") (pin "12") (pinfunction "12_12") (pintype "passive"))
    )
    (net (code "135") (name "VCC_SYS_1") (class "Default")
      (node (ref "JP2") (pin "12") (pinfunction "12_12") (pintype "passive"))
    )
    (net (code "136") (name "unconnected-(IC1-CBUS0-Pad23)") (class "Default")
      (node (ref "IC1") (pin "23") (pinfunction "CBUS0_23") (pintype "bidirectional"))
    )
    (net (code "137") (name "unconnected-(IC1-CBUS1-Pad22)") (class "Default")
      (node (ref "IC1") (pin "22") (pinfunction "CBUS1_22") (pintype "bidirectional"))
    )
    (net (code "138") (name "unconnected-(IC1-CBUS2-Pad13)") (class "Default")
      (node (ref "IC1") (pin "13") (pinfunction "CBUS2_13") (pintype "bidirectional"))
    )
    (net (code "139") (name "unconnected-(IC1-CBUS3-Pad14)") (class "Default")
      (node (ref "IC1") (pin "14") (pinfunction "CBUS3_14") (pintype "bidirectional"))
    )
    (net (code "140") (name "unconnected-(IC1-CBUS4-Pad12)") (class "Default")
      (node (ref "IC1") (pin "12") (pinfunction "CBUS4_12") (pintype "bidirectional"))
    )
    (net (code "141") (name "unconnected-(IC1-OSCI-Pad27)") (class "Default")
      (node (ref "IC1") (pin "27") (pinfunction "OSCI_27") (pintype "input"))
    )
    (net (code "142") (name "unconnected-(IC1-OSCO-Pad28)") (class "Default")
      (node (ref "IC1") (pin "28") (pinfunction "OSCO_28") (pintype "output"))
    )
    (net (code "143") (name "unconnected-(IC1-~{DCD}-Pad10)") (class "Default")
      (node (ref "IC1") (pin "10") (pinfunction "~{DCD}_10") (pintype "input"))
    )
    (net (code "144") (name "unconnected-(IC1-~{DSR}-Pad9)") (class "Default")
      (node (ref "IC1") (pin "9") (pinfunction "~{DSR}_9") (pintype "input"))
    )
    (net (code "145") (name "unconnected-(IC1-~{DTR}-Pad2)") (class "Default")
      (node (ref "IC1") (pin "2") (pinfunction "~{DTR}_2") (pintype "output"))
    )
    (net (code "146") (name "unconnected-(IC1-~{RI}-Pad6)") (class "Default")
      (node (ref "IC1") (pin "6") (pinfunction "~{RI}_6") (pintype "input"))
    )
    (net (code "147") (name "unconnected-(IC2-NC1-Pad6)") (class "Default")
      (node (ref "IC2") (pin "6") (pinfunction "NC1_6") (pintype "bidirectional"))
    )
    (net (code "148") (name "unconnected-(IC2-NC2-Pad8)") (class "Default")
      (node (ref "IC2") (pin "8") (pinfunction "NC2_8") (pintype "bidirectional"))
    )
    (net (code "149") (name "unconnected-(R1-S-PadS@1)") (class "Default")
      (node (ref "R1") (pin "S@1") (pinfunction "S_S@1") (pintype "passive"))
    )
    (net (code "150") (name "unconnected-(R2-S-PadS@1)") (class "Default")
      (node (ref "R2") (pin "S@1") (pinfunction "S_S@1") (pintype "passive"))
    )
    (net (code "151") (name "unconnected-(R3-S-PadS@1)") (class "Default")
      (node (ref "R3") (pin "S@1") (pinfunction "S_S@1") (pintype "passive"))
    )
    (net (code "152") (name "unconnected-(R4-S-PadS@1)") (class "Default")
      (node (ref "R4") (pin "S@1") (pinfunction "S_S@1") (pintype "passive"))
    )
    (net (code "153") (name "unconnected-(R5-S-PadS@1)") (class "Default")
      (node (ref "R5") (pin "S@1") (pinfunction "S_S@1") (pintype "passive"))
    )
    (net (code "154") (name "unconnected-(R6-S-PadS@1)") (class "Default")
      (node (ref "R6") (pin "S@1") (pinfunction "S_S@1") (pintype "passive"))
    )
    (net (code "155") (name "unconnected-(R7-S-PadS@1)") (class "Default")
      (node (ref "R7") (pin "S@1") (pinfunction "S_S@1") (pintype "passive"))
    )
    (net (code "156") (name "unconnected-(U$10-PadA58)") (class "Default")
      (node (ref "U$10") (pin "A58") (pinfunction "A58_A58") (pintype "bidirectional"))
    )
    (net (code "157") (name "unconnected-(U$10-PadA59)") (class "Default")
      (node (ref "U$10") (pin "A59") (pinfunction "A59_A59") (pintype "bidirectional"))
    )
    (net (code "158") (name "unconnected-(U$10-PadB8)") (class "Default")
      (node (ref "U$10") (pin "B8") (pinfunction "B8_B8") (pintype "bidirectional"))
    )
    (net (code "159") (name "unconnected-(U$10-PadB40)") (class "Default")
      (node (ref "U$10") (pin "B40") (pinfunction "B40_B40") (pintype "bidirectional"))
    )
    (net (code "160") (name "unconnected-(U$10-PadB41)") (class "Default")
      (node (ref "U$10") (pin "B41") (pinfunction "B41_B41") (pintype "bidirectional"))
    )
    (net (code "161") (name "unconnected-(U$10-PadB42)") (class "Default")
      (node (ref "U$10") (pin "B42") (pinfunction "B42_B42") (pintype "bidirectional"))
    )
    (net (code "162") (name "unconnected-(U$10-PadB44)") (class "Default")
      (node (ref "U$10") (pin "B44") (pinfunction "B44_B44") (pintype "bidirectional"))
    )
    (net (code "163") (name "unconnected-(U$10-PadB45)") (class "Default")
      (node (ref "U$10") (pin "B45") (pinfunction "B45_B45") (pintype "bidirectional"))
    )
    (net (code "164") (name "unconnected-(U$10-PadB46)") (class "Default")
      (node (ref "U$10") (pin "B46") (pinfunction "B46_B46") (pintype "bidirectional"))
    )
    (net (code "165") (name "unconnected-(U$10-PadB47)") (class "Default")
      (node (ref "U$10") (pin "B47") (pinfunction "B47_B47") (pintype "bidirectional"))
    )
    (net (code "166") (name "unconnected-(U$10-PadB48)") (class "Default")
      (node (ref "U$10") (pin "B48") (pinfunction "B48_B48") (pintype "bidirectional"))
    )
    (net (code "167") (name "unconnected-(U$10-PadB49)") (class "Default")
      (node (ref "U$10") (pin "B49") (pinfunction "B49_B49") (pintype "bidirectional"))
    )
    (net (code "168") (name "unconnected-(U$10-PadB58)") (class "Default")
      (node (ref "U$10") (pin "B58") (pinfunction "B58_B58") (pintype "bidirectional"))
    )
    (net (code "169") (name "unconnected-(U$10-PadB59)") (class "Default")
      (node (ref "U$10") (pin "B59") (pinfunction "B59_B59") (pintype "bidirectional"))
    )
  )
)
